# CI_V_REV_A.net
KiCad netlist of a schematic drawn in EAGLE
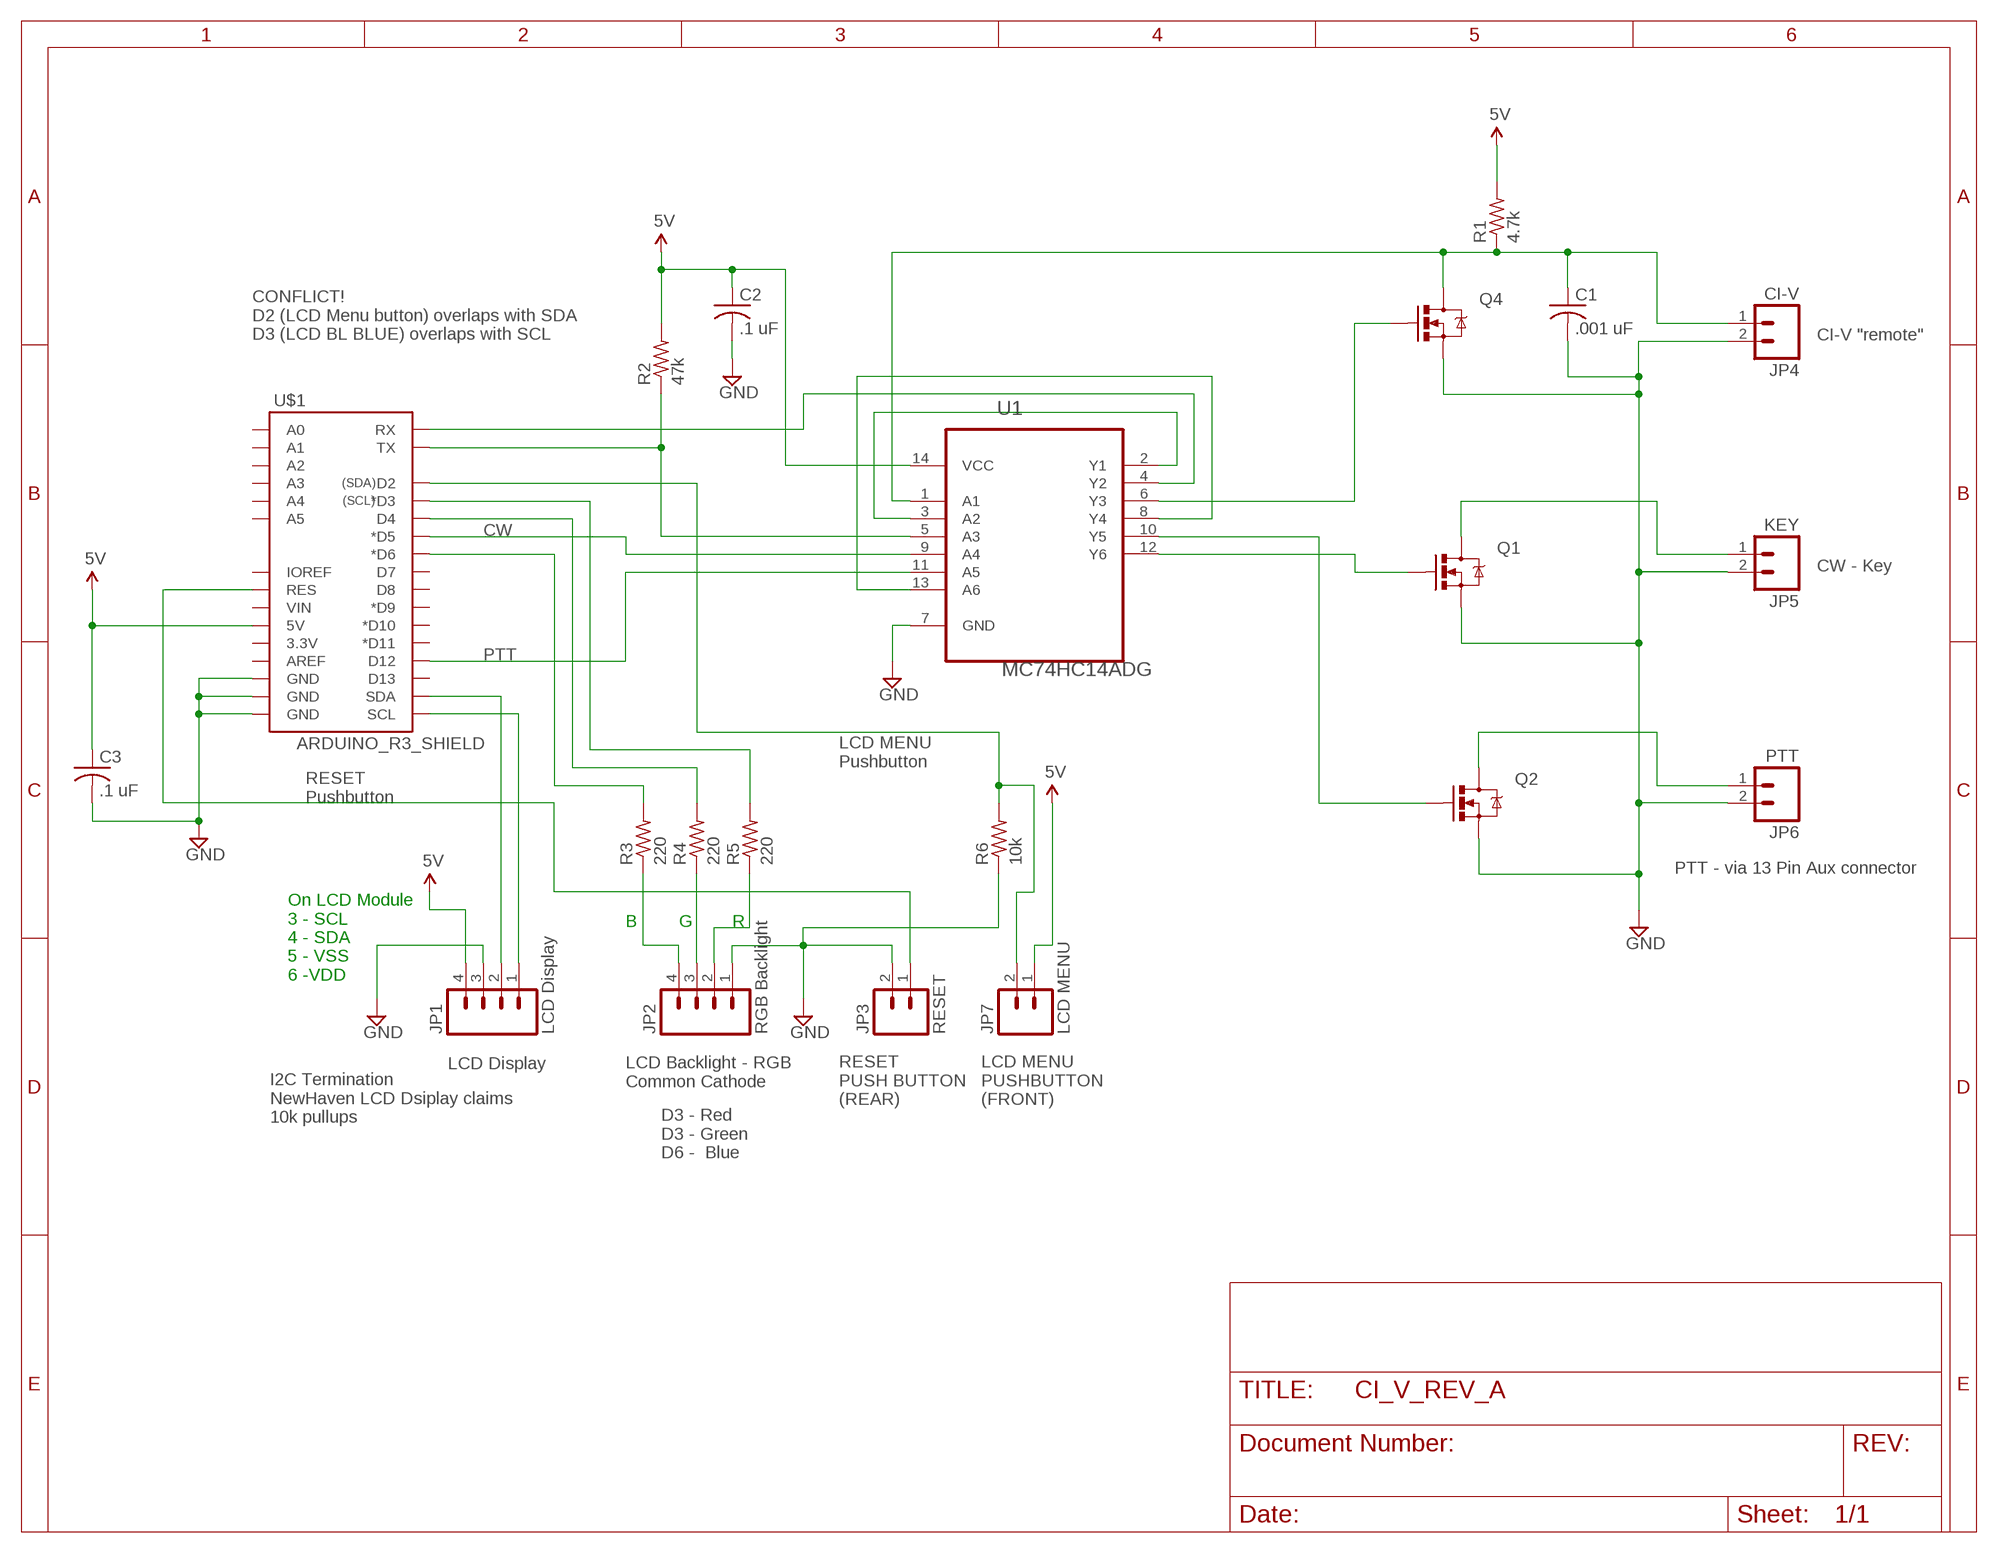
[diagram p0: schematic, sheet 1]

(export (version "E")
  (design (tool "Eeschema 10.0.6"))
  (components
    (comp (ref "C1")
      (value ".001 uF")
      (footprint "eagle-import:C0805")
      (libsource (lib "eagle-import") (part "C-USC0805"))
    )
    (comp (ref "C2")
      (value ".1 uF")
      (footprint "eagle-import:C0805")
      (libsource (lib "eagle-import") (part "C-USC0805"))
    )
    (comp (ref "C3")
      (value ".1 uF")
      (footprint "eagle-import:C0805")
      (libsource (lib "eagle-import") (part "C-USC0805"))
    )
    (comp (ref "JP1")
      (value "LCD Display")
      (footprint "eagle-import:1X04")
      (libsource (lib "eagle-import") (part "M04PTH"))
    )
    (comp (ref "JP2")
      (value "RGB Backlight")
      (footprint "eagle-import:1X04")
      (libsource (lib "eagle-import") (part "M04PTH"))
    )
    (comp (ref "JP3")
      (value "RESET")
      (footprint "eagle-import:1X02")
      (libsource (lib "eagle-import") (part "M02PTH"))
    )
    (comp (ref "JP4")
      (value "CI-V")
      (footprint "eagle-import:1X02")
      (libsource (lib "eagle-import") (part "M02PTH"))
    )
    (comp (ref "JP5")
      (value "KEY")
      (footprint "eagle-import:1X02")
      (libsource (lib "eagle-import") (part "M02PTH"))
    )
    (comp (ref "JP6")
      (value "PTT")
      (footprint "eagle-import:1X02")
      (libsource (lib "eagle-import") (part "M02PTH"))
    )
    (comp (ref "JP7")
      (value "LCD MENU")
      (footprint "eagle-import:1X02")
      (libsource (lib "eagle-import") (part "M02PTH"))
    )
    (comp (ref "Q1")
      (value "MOSFET-NCHANNELBSS123LT1G")
      (footprint "eagle-import:SOT23-3")
      (libsource (lib "eagle-import") (part "MOSFET-NCHANNELBSS123LT1G"))
    )
    (comp (ref "Q2")
      (value "MOSFET-NCHANNELBSS123LT1G")
      (footprint "eagle-import:SOT23-3")
      (libsource (lib "eagle-import") (part "MOSFET-NCHANNELBSS123LT1G"))
    )
    (comp (ref "Q4")
      (value "MOSFET-NCHANNELBSS123LT1G")
      (footprint "eagle-import:SOT23-3")
      (libsource (lib "eagle-import") (part "MOSFET-NCHANNELBSS123LT1G"))
    )
    (comp (ref "R1")
      (value "4.7k")
      (footprint "eagle-import:R0805")
      (libsource (lib "eagle-import") (part "R-US_R0805"))
    )
    (comp (ref "R2")
      (value "47k")
      (footprint "eagle-import:R0805")
      (libsource (lib "eagle-import") (part "R-US_R0805"))
    )
    (comp (ref "R3")
      (value "220")
      (footprint "eagle-import:R0805")
      (libsource (lib "eagle-import") (part "R-US_R0805"))
    )
    (comp (ref "R4")
      (value "220")
      (footprint "eagle-import:R0805")
      (libsource (lib "eagle-import") (part "R-US_R0805"))
    )
    (comp (ref "R5")
      (value "220")
      (footprint "eagle-import:R0805")
      (libsource (lib "eagle-import") (part "R-US_R0805"))
    )
    (comp (ref "R6")
      (value "10k")
      (footprint "eagle-import:R0805")
      (libsource (lib "eagle-import") (part "R-US_R0805"))
    )
    (comp (ref "U$1")
      (value "ARDUINO_R3_SHIELD")
      (footprint "eagle-import:UNO_R3_SHIELD")
      (libsource (lib "eagle-import") (part "ARDUINO_R3_SHIELD"))
    )
    (comp (ref "U1")
      (value "MC74HC14ADG")
      (footprint "eagle-import:SOIC127P600X175-14N")
      (libsource (lib "eagle-import") (part "MC74HC14ADG"))
    )
  )
  (nets
    (net (code "1") (name "/CW") (class "Default")
      (node (ref "U$1") (pin "D5") (pinfunction "*D5_D5") (pintype "bidirectional"))
      (node (ref "U1") (pin "9") (pinfunction "A4_9") (pintype "input"))
    )
    (net (code "2") (name "/PTT") (class "Default")
      (node (ref "U$1") (pin "D12") (pinfunction "D12_D12") (pintype "bidirectional"))
      (node (ref "U1") (pin "11") (pinfunction "A5_11") (pintype "input"))
    )
    (net (code "3") (name "5V") (class "Default")
      (node (ref "C2") (pin "1") (pinfunction "1_1") (pintype "passive"))
      (node (ref "C3") (pin "1") (pinfunction "1_1") (pintype "passive"))
      (node (ref "JP1") (pin "4") (pinfunction "4_4") (pintype "passive"))
      (node (ref "JP7") (pin "1") (pinfunction "1_1") (pintype "passive"))
      (node (ref "R1") (pin "2") (pinfunction "2_2") (pintype "passive"))
      (node (ref "R2") (pin "2") (pinfunction "2_2") (pintype "passive"))
      (node (ref "U$1") (pin "5V") (pinfunction "5V_5V") (pintype "bidirectional"))
      (node (ref "U1") (pin "14") (pinfunction "VCC_14") (pintype "power_in"))
    )
    (net (code "4") (name "GND") (class "Default")
      (node (ref "C1") (pin "2") (pinfunction "2_2") (pintype "passive"))
      (node (ref "C2") (pin "2") (pinfunction "2_2") (pintype "passive"))
      (node (ref "C3") (pin "2") (pinfunction "2_2") (pintype "passive"))
      (node (ref "JP1") (pin "3") (pinfunction "3_3") (pintype "passive"))
      (node (ref "JP2") (pin "1") (pinfunction "1_1") (pintype "passive"))
      (node (ref "JP3") (pin "2") (pinfunction "2_2") (pintype "passive"))
      (node (ref "JP4") (pin "2") (pinfunction "2_2") (pintype "passive"))
      (node (ref "JP5") (pin "2") (pinfunction "2_2") (pintype "passive"))
      (node (ref "JP6") (pin "2") (pinfunction "2_2") (pintype "passive"))
      (node (ref "Q1") (pin "2") (pinfunction "S_2") (pintype "passive"))
      (node (ref "Q2") (pin "2") (pinfunction "S_2") (pintype "passive"))
      (node (ref "Q4") (pin "2") (pinfunction "S_2") (pintype "passive"))
      (node (ref "R6") (pin "1") (pinfunction "1_1") (pintype "passive"))
      (node (ref "U$1") (pin "GND@0") (pinfunction "GND_GND@0") (pintype "bidirectional"))
      (node (ref "U$1") (pin "GND@1") (pinfunction "GND_GND@1") (pintype "bidirectional"))
      (node (ref "U$1") (pin "GND@2") (pinfunction "GND_GND@2") (pintype "bidirectional"))
      (node (ref "U1") (pin "7") (pinfunction "GND_7") (pintype "passive"))
    )
    (net (code "5") (name "Net-(JP1-Pad1)") (class "Default")
      (node (ref "JP1") (pin "1") (pinfunction "1_1") (pintype "passive"))
      (node (ref "U$1") (pin "SCL") (pinfunction "SCL_SCL") (pintype "bidirectional"))
    )
    (net (code "6") (name "Net-(JP1-Pad2)") (class "Default")
      (node (ref "JP1") (pin "2") (pinfunction "2_2") (pintype "passive"))
      (node (ref "U$1") (pin "SDA") (pinfunction "SDA_SDA") (pintype "bidirectional"))
    )
    (net (code "7") (name "Net-(JP2-Pad2)") (class "Default")
      (node (ref "JP2") (pin "2") (pinfunction "2_2") (pintype "passive"))
      (node (ref "R5") (pin "1") (pinfunction "1_1") (pintype "passive"))
    )
    (net (code "8") (name "Net-(JP2-Pad3)") (class "Default")
      (node (ref "JP2") (pin "3") (pinfunction "3_3") (pintype "passive"))
      (node (ref "R4") (pin "1") (pinfunction "1_1") (pintype "passive"))
    )
    (net (code "9") (name "Net-(JP2-Pad4)") (class "Default")
      (node (ref "JP2") (pin "4") (pinfunction "4_4") (pintype "passive"))
      (node (ref "R3") (pin "1") (pinfunction "1_1") (pintype "passive"))
    )
    (net (code "10") (name "Net-(JP3-Pad1)") (class "Default")
      (node (ref "JP3") (pin "1") (pinfunction "1_1") (pintype "passive"))
      (node (ref "U$1") (pin "RES") (pinfunction "RES_RES") (pintype "bidirectional"))
    )
    (net (code "11") (name "Net-(JP7-Pad2)") (class "Default")
      (node (ref "JP7") (pin "2") (pinfunction "2_2") (pintype "passive"))
      (node (ref "R6") (pin "2") (pinfunction "2_2") (pintype "passive"))
      (node (ref "U$1") (pin "D2") (pinfunction "D2_D2") (pintype "bidirectional"))
    )
    (net (code "12") (name "Net-(Q1-D)") (class "Default")
      (node (ref "JP5") (pin "1") (pinfunction "1_1") (pintype "passive"))
      (node (ref "Q1") (pin "3") (pinfunction "D_3") (pintype "passive"))
    )
    (net (code "13") (name "Net-(Q1-G)") (class "Default")
      (node (ref "Q1") (pin "1") (pinfunction "G_1") (pintype "passive"))
      (node (ref "U1") (pin "12") (pinfunction "Y6_12") (pintype "output"))
    )
    (net (code "14") (name "Net-(Q2-D)") (class "Default")
      (node (ref "JP6") (pin "1") (pinfunction "1_1") (pintype "passive"))
      (node (ref "Q2") (pin "3") (pinfunction "D_3") (pintype "passive"))
    )
    (net (code "15") (name "Net-(Q2-G)") (class "Default")
      (node (ref "Q2") (pin "1") (pinfunction "G_1") (pintype "passive"))
      (node (ref "U1") (pin "10") (pinfunction "Y5_10") (pintype "output"))
    )
    (net (code "16") (name "Net-(Q4-D)") (class "Default")
      (node (ref "C1") (pin "1") (pinfunction "1_1") (pintype "passive"))
      (node (ref "JP4") (pin "1") (pinfunction "1_1") (pintype "passive"))
      (node (ref "Q4") (pin "3") (pinfunction "D_3") (pintype "passive"))
      (node (ref "R1") (pin "1") (pinfunction "1_1") (pintype "passive"))
      (node (ref "U1") (pin "1") (pinfunction "A1_1") (pintype "input"))
    )
    (net (code "17") (name "Net-(Q4-G)") (class "Default")
      (node (ref "Q4") (pin "1") (pinfunction "G_1") (pintype "passive"))
      (node (ref "U1") (pin "6") (pinfunction "Y3_6") (pintype "output"))
    )
    (net (code "18") (name "Net-(R4-Pad2)") (class "Default")
      (node (ref "R4") (pin "2") (pinfunction "2_2") (pintype "passive"))
      (node (ref "U$1") (pin "D4") (pinfunction "D4_D4") (pintype "bidirectional"))
    )
    (net (code "19") (name "Net-(U$1-*D3)") (class "Default")
      (node (ref "R5") (pin "2") (pinfunction "2_2") (pintype "passive"))
      (node (ref "U$1") (pin "D3") (pinfunction "*D3_D3") (pintype "bidirectional"))
    )
    (net (code "20") (name "Net-(U$1-*D6)") (class "Default")
      (node (ref "R3") (pin "2") (pinfunction "2_2") (pintype "passive"))
      (node (ref "U$1") (pin "D6") (pinfunction "*D6_D6") (pintype "bidirectional"))
    )
    (net (code "21") (name "Net-(U1-A2)") (class "Default")
      (node (ref "U1") (pin "2") (pinfunction "Y1_2") (pintype "output"))
      (node (ref "U1") (pin "3") (pinfunction "A2_3") (pintype "input"))
    )
    (net (code "22") (name "Net-(U1-A3)") (class "Default")
      (node (ref "R2") (pin "1") (pinfunction "1_1") (pintype "passive"))
      (node (ref "U$1") (pin "TX") (pinfunction "TX_TX") (pintype "bidirectional"))
      (node (ref "U1") (pin "5") (pinfunction "A3_5") (pintype "input"))
    )
    (net (code "23") (name "Net-(U1-A6)") (class "Default")
      (node (ref "U1") (pin "13") (pinfunction "A6_13") (pintype "input"))
      (node (ref "U1") (pin "8") (pinfunction "Y4_8") (pintype "output"))
    )
    (net (code "24") (name "Net-(U1-Y2)") (class "Default")
      (node (ref "U$1") (pin "RX") (pinfunction "RX_RX") (pintype "bidirectional"))
      (node (ref "U1") (pin "4") (pinfunction "Y2_4") (pintype "output"))
    )
    (net (code "25") (name "unconnected-(U$1-*D9-PadD9)") (class "Default")
      (node (ref "U$1") (pin "D9") (pinfunction "*D9_D9") (pintype "bidirectional"))
    )
    (net (code "26") (name "unconnected-(U$1-*D10-PadD10)") (class "Default")
      (node (ref "U$1") (pin "D10") (pinfunction "*D10_D10") (pintype "bidirectional"))
    )
    (net (code "27") (name "unconnected-(U$1-*D11-PadD11)") (class "Default")
      (node (ref "U$1") (pin "D11") (pinfunction "*D11_D11") (pintype "bidirectional"))
    )
    (net (code "28") (name "unconnected-(U$1-Pad3.3V)") (class "Default")
      (node (ref "U$1") (pin "3.3V") (pinfunction "3.3V_3.3V") (pintype "bidirectional"))
    )
    (net (code "29") (name "unconnected-(U$1-PadA0)") (class "Default")
      (node (ref "U$1") (pin "A0") (pinfunction "A0_A0") (pintype "bidirectional"))
    )
    (net (code "30") (name "unconnected-(U$1-PadA1)") (class "Default")
      (node (ref "U$1") (pin "A1") (pinfunction "A1_A1") (pintype "bidirectional"))
    )
    (net (code "31") (name "unconnected-(U$1-PadA2)") (class "Default")
      (node (ref "U$1") (pin "A2") (pinfunction "A2_A2") (pintype "bidirectional"))
    )
    (net (code "32") (name "unconnected-(U$1-PadA3)") (class "Default")
      (node (ref "U$1") (pin "A3") (pinfunction "A3_A3") (pintype "bidirectional"))
    )
    (net (code "33") (name "unconnected-(U$1-PadA4)") (class "Default")
      (node (ref "U$1") (pin "A4") (pinfunction "A4_A4") (pintype "bidirectional"))
    )
    (net (code "34") (name "unconnected-(U$1-PadA5)") (class "Default")
      (node (ref "U$1") (pin "A5") (pinfunction "A5_A5") (pintype "bidirectional"))
    )
    (net (code "35") (name "unconnected-(U$1-PadAREF)") (class "Default")
      (node (ref "U$1") (pin "AREF") (pinfunction "AREF_AREF") (pintype "bidirectional"))
    )
    (net (code "36") (name "unconnected-(U$1-PadD7)") (class "Default")
      (node (ref "U$1") (pin "D7") (pinfunction "D7_D7") (pintype "bidirectional"))
    )
    (net (code "37") (name "unconnected-(U$1-PadD8)") (class "Default")
      (node (ref "U$1") (pin "D8") (pinfunction "D8_D8") (pintype "bidirectional"))
    )
    (net (code "38") (name "unconnected-(U$1-PadD13)") (class "Default")
      (node (ref "U$1") (pin "D13") (pinfunction "D13_D13") (pintype "bidirectional"))
    )
    (net (code "39") (name "unconnected-(U$1-PadIOREF)") (class "Default")
      (node (ref "U$1") (pin "IOREF") (pinfunction "IOREF_IOREF") (pintype "bidirectional"))
    )
    (net (code "40") (name "unconnected-(U$1-PadVIN)") (class "Default")
      (node (ref "U$1") (pin "VIN") (pinfunction "VIN_VIN") (pintype "bidirectional"))
    )
  )
)
